# esp32-s2_ePaper_pcb_v1.net
KiCad netlist of a schematic drawn in EAGLE
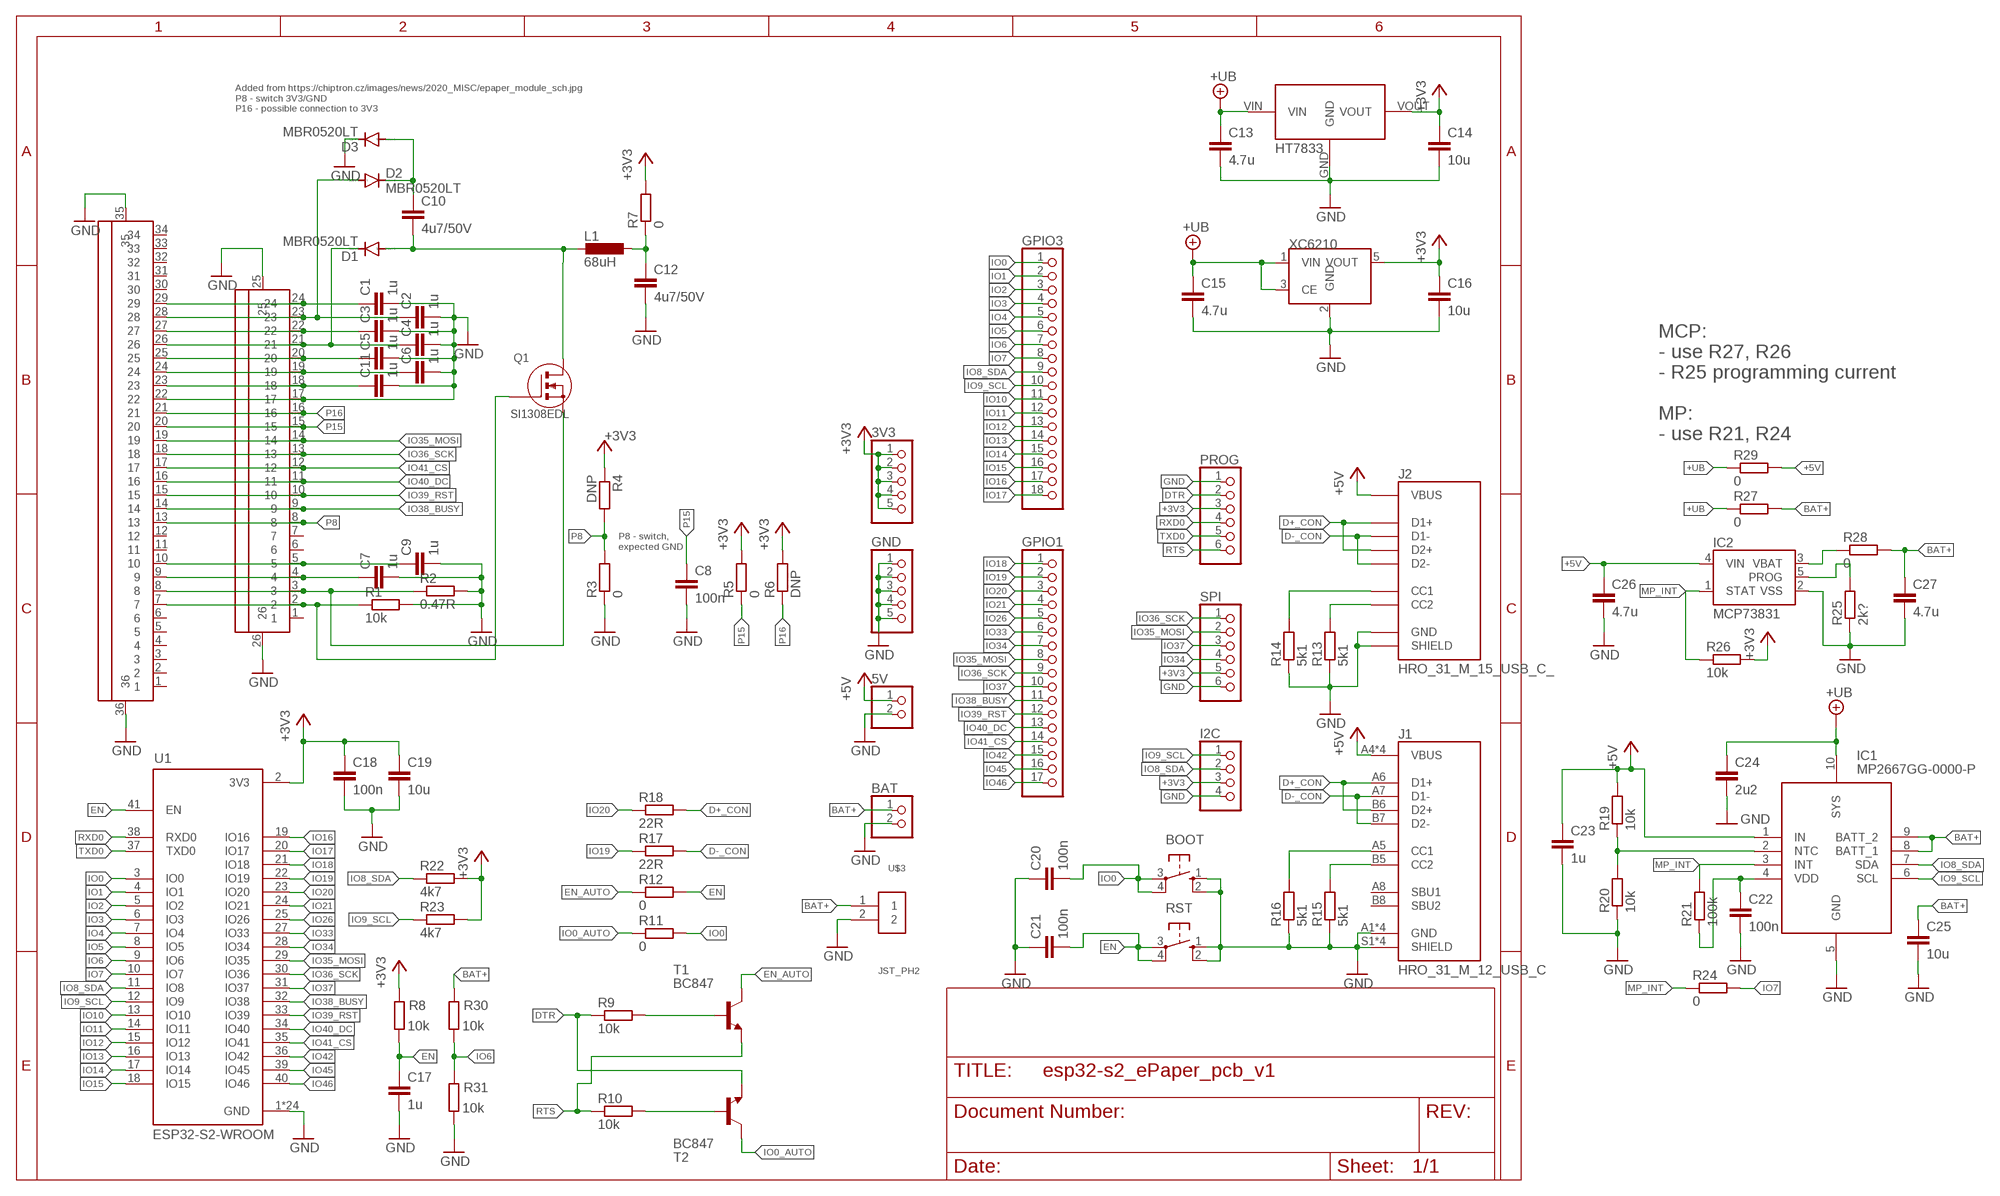
[diagram p0: schematic, sheet 1]

(export (version "E")
  (design (tool "Eeschema 10.0.6"))
  (components
    (comp (ref "3V3")
      (value "PINHD-1X5")
      (footprint "eagle-import:1X05")
      (libsource (lib "eagle-import") (part "PINHD-1X5"))
    )
    (comp (ref "5V")
      (value "PINHD-1X2")
      (footprint "eagle-import:1X02")
      (libsource (lib "eagle-import") (part "PINHD-1X2"))
    )
    (comp (ref "BAT")
      (value "PINHD-1X2")
      (footprint "eagle-import:1X02")
      (libsource (lib "eagle-import") (part "PINHD-1X2"))
    )
    (comp (ref "BOOT")
      (value "10-XX")
      (footprint "eagle-import:B3F-10XX")
      (fields (field (name "MPN") "B3F-1000"))
      (libsource (lib "eagle-import") (part "10-XX"))
    )
    (comp (ref "C1")
      (value "1u")
      (footprint "eagle-import:C0603K")
      (libsource (lib "eagle-import") (part "C-EUC0603K"))
    )
    (comp (ref "C2")
      (value "1u")
      (footprint "eagle-import:C0603K")
      (libsource (lib "eagle-import") (part "C-EUC0603K"))
    )
    (comp (ref "C3")
      (value "1u")
      (footprint "eagle-import:C0603K")
      (libsource (lib "eagle-import") (part "C-EUC0603K"))
    )
    (comp (ref "C4")
      (value "1u")
      (footprint "eagle-import:C0603K")
      (libsource (lib "eagle-import") (part "C-EUC0603K"))
    )
    (comp (ref "C5")
      (value "1u")
      (footprint "eagle-import:C0603K")
      (libsource (lib "eagle-import") (part "C-EUC0603K"))
    )
    (comp (ref "C6")
      (value "1u")
      (footprint "eagle-import:C0603K")
      (libsource (lib "eagle-import") (part "C-EUC0603K"))
    )
    (comp (ref "C7")
      (value "1u")
      (footprint "eagle-import:C0603K")
      (libsource (lib "eagle-import") (part "C-EUC0603K"))
    )
    (comp (ref "C8")
      (value "100n")
      (footprint "eagle-import:C0603K")
      (libsource (lib "eagle-import") (part "C-EUC0603K"))
    )
    (comp (ref "C9")
      (value "1u")
      (footprint "eagle-import:C0603K")
      (libsource (lib "eagle-import") (part "C-EUC0603K"))
    )
    (comp (ref "C10")
      (value "4u7/50V")
      (footprint "eagle-import:C1206")
      (libsource (lib "eagle-import") (part "C-EUC1206"))
    )
    (comp (ref "C11")
      (value "1u")
      (footprint "eagle-import:C0603K")
      (libsource (lib "eagle-import") (part "C-EUC0603K"))
    )
    (comp (ref "C12")
      (value "4u7/50V")
      (footprint "eagle-import:C1206")
      (libsource (lib "eagle-import") (part "C-EUC1206"))
    )
    (comp (ref "C13")
      (value "4.7u")
      (footprint "eagle-import:C1206")
      (libsource (lib "eagle-import") (part "C-EUC1206"))
    )
    (comp (ref "C14")
      (value "10u")
      (footprint "eagle-import:C1206")
      (libsource (lib "eagle-import") (part "C-EUC1206"))
    )
    (comp (ref "C15")
      (value "4.7u")
      (footprint "eagle-import:C1206")
      (libsource (lib "eagle-import") (part "C-EUC1206"))
    )
    (comp (ref "C16")
      (value "10u")
      (footprint "eagle-import:C1206")
      (libsource (lib "eagle-import") (part "C-EUC1206"))
    )
    (comp (ref "C17")
      (value "1u")
      (footprint "eagle-import:C0603K")
      (libsource (lib "eagle-import") (part "C-EUC0603K"))
    )
    (comp (ref "C18")
      (value "100n")
      (footprint "eagle-import:C0603K")
      (libsource (lib "eagle-import") (part "C-EUC0603K"))
    )
    (comp (ref "C19")
      (value "10u")
      (footprint "eagle-import:C1206")
      (libsource (lib "eagle-import") (part "C-EUC1206"))
    )
    (comp (ref "C20")
      (value "100n")
      (footprint "eagle-import:C0603K")
      (libsource (lib "eagle-import") (part "C-EUC0603K"))
    )
    (comp (ref "C21")
      (value "100n")
      (footprint "eagle-import:C0603K")
      (libsource (lib "eagle-import") (part "C-EUC0603K"))
    )
    (comp (ref "C22")
      (value "100n")
      (footprint "eagle-import:C0603K")
      (libsource (lib "eagle-import") (part "C-EUC0603K"))
    )
    (comp (ref "C23")
      (value "1u")
      (footprint "eagle-import:C0603K")
      (libsource (lib "eagle-import") (part "C-EUC0603K"))
    )
    (comp (ref "C24")
      (value "2u2")
      (footprint "eagle-import:C1206")
      (libsource (lib "eagle-import") (part "C-EUC1206"))
    )
    (comp (ref "C25")
      (value "10u")
      (footprint "eagle-import:C1206")
      (libsource (lib "eagle-import") (part "C-EUC1206"))
    )
    (comp (ref "C26")
      (value "4.7u")
      (footprint "eagle-import:C1206")
      (libsource (lib "eagle-import") (part "C-EUC1206"))
    )
    (comp (ref "C27")
      (value "4.7u")
      (footprint "eagle-import:C1206")
      (libsource (lib "eagle-import") (part "C-EUC1206"))
    )
    (comp (ref "D1")
      (value "MBR0520LT")
      (footprint "eagle-import:SOD123")
      (libsource (lib "eagle-import") (part "MBR0520LT"))
    )
    (comp (ref "D2")
      (value "MBR0520LT")
      (footprint "eagle-import:SOD123")
      (libsource (lib "eagle-import") (part "MBR0520LT"))
    )
    (comp (ref "D3")
      (value "MBR0520LT")
      (footprint "eagle-import:SOD123")
      (libsource (lib "eagle-import") (part "MBR0520LT"))
    )
    (comp (ref "GND")
      (value "PINHD-1X5")
      (footprint "eagle-import:1X05")
      (libsource (lib "eagle-import") (part "PINHD-1X5"))
    )
    (comp (ref "GPIO1")
      (value "PINHD-1X17")
      (footprint "eagle-import:1X17")
      (libsource (lib "eagle-import") (part "PINHD-1X17"))
    )
    (comp (ref "GPIO3")
      (value "PINHD-1X18")
      (footprint "eagle-import:1X18")
      (libsource (lib "eagle-import") (part "PINHD-1X18"))
    )
    (comp (ref "I2C")
      (value "PINHD-1X4")
      (footprint "eagle-import:1X04")
      (libsource (lib "eagle-import") (part "PINHD-1X4"))
    )
    (comp (ref "IC1")
      (value "MP2667GG-0000-P")
      (footprint "eagle-import:QFN50P200X200X105-10N")
      (fields (field (name "MOUSER_PART_NUMBER") "946-MP2667GG-0000-P"))
      (libsource (lib "eagle-import") (part "MP2667GG-0000-P"))
    )
    (comp (ref "IC2")
      (value "MCP73831")
      (footprint "eagle-import:SOT95P290X120-5")
      (libsource (lib "eagle-import") (part "MCP73831"))
    )
    (comp (ref "J1")
      (value "HRO_31_M_12_USB_C")
      (footprint "eagle-import:HRO_31_M_12_USB_C")
      (libsource (lib "eagle-import") (part "HRO_31_M_12_USB_C"))
    )
    (comp (ref "J2")
      (value "HRO_31_M_15_USB_C_")
      (footprint "eagle-import:HRO_31_M_15_USB_C")
      (libsource (lib "eagle-import") (part "HRO_31_M_15_USB_C_"))
    )
    (comp (ref "L1")
      (value "68uH")
      (footprint "eagle-import:L4532P")
      (libsource (lib "eagle-import") (part "L-EUL4532P"))
    )
    (comp (ref "PROG")
      (value "PINHD-1X6")
      (footprint "eagle-import:1X06")
      (libsource (lib "eagle-import") (part "PINHD-1X6"))
    )
    (comp (ref "Q1")
      (value "SI1308EDL")
      (footprint "eagle-import:SC-70")
      (libsource (lib "eagle-import") (part "SI1308EDL"))
    )
    (comp (ref "R1")
      (value "10k")
      (footprint "eagle-import:R0603")
      (libsource (lib "eagle-import") (part "R-EU_R0603"))
    )
    (comp (ref "R2")
      (value "0.47R")
      (footprint "eagle-import:R0603")
      (libsource (lib "eagle-import") (part "R-EU_R0603"))
    )
    (comp (ref "R3")
      (value "0")
      (footprint "eagle-import:R0603")
      (libsource (lib "eagle-import") (part "R-EU_R0603"))
    )
    (comp (ref "R4")
      (value "DNP")
      (footprint "eagle-import:R0603")
      (libsource (lib "eagle-import") (part "R-EU_R0603"))
    )
    (comp (ref "R5")
      (value "0")
      (footprint "eagle-import:R0603")
      (libsource (lib "eagle-import") (part "R-EU_R0603"))
    )
    (comp (ref "R6")
      (value "DNP")
      (footprint "eagle-import:R0603")
      (libsource (lib "eagle-import") (part "R-EU_R0603"))
    )
    (comp (ref "R7")
      (value "0")
      (footprint "eagle-import:R0603")
      (libsource (lib "eagle-import") (part "R-EU_R0603"))
    )
    (comp (ref "R8")
      (value "10k")
      (footprint "eagle-import:R0603")
      (libsource (lib "eagle-import") (part "R-EU_R0603"))
    )
    (comp (ref "R9")
      (value "10k")
      (footprint "eagle-import:R0603")
      (libsource (lib "eagle-import") (part "R-EU_R0603"))
    )
    (comp (ref "R10")
      (value "10k")
      (footprint "eagle-import:R0603")
      (libsource (lib "eagle-import") (part "R-EU_R0603"))
    )
    (comp (ref "R11")
      (value "0")
      (footprint "eagle-import:R0603")
      (libsource (lib "eagle-import") (part "R-EU_R0603"))
    )
    (comp (ref "R12")
      (value "0")
      (footprint "eagle-import:R0603")
      (libsource (lib "eagle-import") (part "R-EU_R0603"))
    )
    (comp (ref "R13")
      (value "5k1")
      (footprint "eagle-import:R0603")
      (libsource (lib "eagle-import") (part "R-EU_R0603"))
    )
    (comp (ref "R14")
      (value "5k1")
      (footprint "eagle-import:R0603")
      (libsource (lib "eagle-import") (part "R-EU_R0603"))
    )
    (comp (ref "R15")
      (value "5k1")
      (footprint "eagle-import:R0603")
      (libsource (lib "eagle-import") (part "R-EU_R0603"))
    )
    (comp (ref "R16")
      (value "5k1")
      (footprint "eagle-import:R0603")
      (libsource (lib "eagle-import") (part "R-EU_R0603"))
    )
    (comp (ref "R17")
      (value "22R")
      (footprint "eagle-import:R0603")
      (libsource (lib "eagle-import") (part "R-EU_R0603"))
    )
    (comp (ref "R18")
      (value "22R")
      (footprint "eagle-import:R0603")
      (libsource (lib "eagle-import") (part "R-EU_R0603"))
    )
    (comp (ref "R19")
      (value "10k")
      (footprint "eagle-import:R0603")
      (libsource (lib "eagle-import") (part "R-EU_R0603"))
    )
    (comp (ref "R20")
      (value "10k")
      (footprint "eagle-import:R0603")
      (libsource (lib "eagle-import") (part "R-EU_R0603"))
    )
    (comp (ref "R21")
      (value "100k")
      (footprint "eagle-import:R0603")
      (libsource (lib "eagle-import") (part "R-EU_R0603"))
    )
    (comp (ref "R22")
      (value "4k7")
      (footprint "eagle-import:R0603")
      (libsource (lib "eagle-import") (part "R-EU_R0603"))
    )
    (comp (ref "R23")
      (value "4k7")
      (footprint "eagle-import:R0603")
      (libsource (lib "eagle-import") (part "R-EU_R0603"))
    )
    (comp (ref "R24")
      (value "0")
      (footprint "eagle-import:R0603")
      (libsource (lib "eagle-import") (part "R-EU_R0603"))
    )
    (comp (ref "R25")
      (value "2k?")
      (footprint "eagle-import:R0603")
      (libsource (lib "eagle-import") (part "R-EU_R0603"))
    )
    (comp (ref "R26")
      (value "10k")
      (footprint "eagle-import:R0603")
      (libsource (lib "eagle-import") (part "R-EU_R0603"))
    )
    (comp (ref "R27")
      (value "0")
      (footprint "eagle-import:R0603")
      (libsource (lib "eagle-import") (part "R-EU_R0603"))
    )
    (comp (ref "R28")
      (value "0")
      (footprint "eagle-import:R0603")
      (libsource (lib "eagle-import") (part "R-EU_R0603"))
    )
    (comp (ref "R29")
      (value "0")
      (footprint "eagle-import:R0603")
      (libsource (lib "eagle-import") (part "R-EU_R0603"))
    )
    (comp (ref "R30")
      (value "10k")
      (footprint "eagle-import:R0603")
      (libsource (lib "eagle-import") (part "R-EU_R0603"))
    )
    (comp (ref "R31")
      (value "10k")
      (footprint "eagle-import:R0603")
      (libsource (lib "eagle-import") (part "R-EU_R0603"))
    )
    (comp (ref "RST")
      (value "10-XX")
      (footprint "eagle-import:B3F-10XX")
      (fields (field (name "MPN") "B3F-1000"))
      (libsource (lib "eagle-import") (part "10-XX"))
    )
    (comp (ref "SPI")
      (value "PINHD-1X6")
      (footprint "eagle-import:1X06")
      (libsource (lib "eagle-import") (part "PINHD-1X6"))
    )
    (comp (ref "T1")
      (value "BC847")
      (footprint "eagle-import:SOT23")
      (libsource (lib "eagle-import") (part "BC847"))
    )
    (comp (ref "T2")
      (value "BC847")
      (footprint "eagle-import:SOT23")
      (libsource (lib "eagle-import") (part "BC847"))
    )
    (comp (ref "U$1")
      (value "AYF532435_FPC_24PIN_0.5")
      (footprint "eagle-import:FPC_0.5_24PIN")
      (libsource (lib "eagle-import") (part "AYF532435_FPC_24PIN_0.5"))
    )
    (comp (ref "U$2")
      (value "AYF533435_FPC_34PIN_0.5")
      (footprint "eagle-import:FPC_0.5_34PIN")
      (libsource (lib "eagle-import") (part "AYF533435_FPC_34PIN_0.5"))
    )
    (comp (ref "U$3")
      (value "JST_PH2")
      (footprint "eagle-import:JSTPH2")
      (libsource (lib "eagle-import") (part "JST_PH2"))
    )
    (comp (ref "U1")
      (value "ESP32-S2-WROOM")
      (footprint "eagle-import:XCVR_ESP32-S2-WROOM")
      (fields (field (name "MF") "Espressif Systems"))
      (libsource (lib "eagle-import") (part "ESP32-S2-WROOM"))
    )
    (comp (ref "U2")
      (value "HT7833")
      (footprint "eagle-import:SOT89")
      (libsource (lib "eagle-import") (part "HT7833"))
    )
    (comp (ref "U3")
      (value "XC6210")
      (footprint "eagle-import:SOT-23-5")
      (libsource (lib "eagle-import") (part "XC6210"))
    )
  )
  (nets
    (net (code "1") (name "+3V3") (class "Default")
      (node (ref "3V3") (pin "1") (pinfunction "1_1") (pintype "passive"))
      (node (ref "3V3") (pin "2") (pinfunction "2_2") (pintype "passive"))
      (node (ref "3V3") (pin "3") (pinfunction "3_3") (pintype "passive"))
      (node (ref "3V3") (pin "4") (pinfunction "4_4") (pintype "passive"))
      (node (ref "3V3") (pin "5") (pinfunction "5_5") (pintype "passive"))
      (node (ref "C14") (pin "1") (pinfunction "1_1") (pintype "passive"))
      (node (ref "C16") (pin "1") (pinfunction "1_1") (pintype "passive"))
      (node (ref "C18") (pin "1") (pinfunction "1_1") (pintype "passive"))
      (node (ref "C19") (pin "1") (pinfunction "1_1") (pintype "passive"))
      (node (ref "I2C") (pin "3") (pinfunction "3_3") (pintype "passive"))
      (node (ref "PROG") (pin "3") (pinfunction "3_3") (pintype "passive"))
      (node (ref "R22") (pin "2") (pinfunction "2_2") (pintype "passive"))
      (node (ref "R23") (pin "2") (pinfunction "2_2") (pintype "passive"))
      (node (ref "R26") (pin "2") (pinfunction "2_2") (pintype "passive"))
      (node (ref "R4") (pin "1") (pinfunction "1_1") (pintype "passive"))
      (node (ref "R5") (pin "2") (pinfunction "2_2") (pintype "passive"))
      (node (ref "R6") (pin "2") (pinfunction "2_2") (pintype "passive"))
      (node (ref "R7") (pin "2") (pinfunction "2_2") (pintype "passive"))
      (node (ref "R8") (pin "2") (pinfunction "2_2") (pintype "passive"))
      (node (ref "SPI") (pin "5") (pinfunction "5_5") (pintype "passive"))
      (node (ref "U1") (pin "2") (pinfunction "3V3_2") (pintype "power_in"))
      (node (ref "U2") (pin "VOUT") (pinfunction "VOUT_VOUT") (pintype "bidirectional"))
      (node (ref "U3") (pin "5") (pinfunction "VOUT_5") (pintype "power_in"))
    )
    (net (code "2") (name "+5V") (class "Default")
      (node (ref "5V") (pin "1") (pinfunction "1_1") (pintype "passive"))
      (node (ref "C23") (pin "1") (pinfunction "1_1") (pintype "passive"))
      (node (ref "C26") (pin "1") (pinfunction "1_1") (pintype "passive"))
      (node (ref "IC1") (pin "1") (pinfunction "IN_1") (pintype "bidirectional"))
      (node (ref "IC2") (pin "4") (pinfunction "VIN_4") (pintype "power_in"))
      (node (ref "J1") (pin "A4") (pinfunction "VBUS_A4") (pintype "passive"))
      (node (ref "J1") (pin "A9") (pinfunction "VBUS_A9") (pintype "passive"))
      (node (ref "J1") (pin "B4") (pinfunction "VBUS_B4") (pintype "passive"))
      (node (ref "J1") (pin "B9") (pinfunction "VBUS_B9") (pintype "passive"))
      (node (ref "J2") (pin "P$13") (pinfunction "VBUS_P$13") (pintype "passive"))
      (node (ref "J2") (pin "P$2") (pinfunction "VBUS_P$2") (pintype "passive"))
      (node (ref "J2") (pin "P$6") (pinfunction "VBUS_P$6") (pintype "passive"))
      (node (ref "J2") (pin "P$9") (pinfunction "VBUS_P$9") (pintype "passive"))
      (node (ref "R19") (pin "2") (pinfunction "2_2") (pintype "passive"))
      (node (ref "R29") (pin "2") (pinfunction "2_2") (pintype "passive"))
    )
    (net (code "3") (name "+UB") (class "Default")
      (node (ref "C13") (pin "1") (pinfunction "1_1") (pintype "passive"))
      (node (ref "C15") (pin "1") (pinfunction "1_1") (pintype "passive"))
      (node (ref "C24") (pin "1") (pinfunction "1_1") (pintype "passive"))
      (node (ref "IC1") (pin "10") (pinfunction "SYS_10") (pintype "bidirectional"))
      (node (ref "R27") (pin "1") (pinfunction "1_1") (pintype "passive"))
      (node (ref "R29") (pin "1") (pinfunction "1_1") (pintype "passive"))
      (node (ref "U2") (pin "VIN") (pinfunction "VIN_VIN") (pintype "bidirectional"))
      (node (ref "U3") (pin "1") (pinfunction "VIN_1") (pintype "power_in"))
      (node (ref "U3") (pin "3") (pinfunction "CE_3") (pintype "power_in"))
    )
    (net (code "4") (name "BAT+") (class "Default")
      (node (ref "BAT") (pin "1") (pinfunction "1_1") (pintype "passive"))
      (node (ref "C25") (pin "1") (pinfunction "1_1") (pintype "passive"))
      (node (ref "C27") (pin "1") (pinfunction "1_1") (pintype "passive"))
      (node (ref "IC1") (pin "8") (pinfunction "BATT_1_8") (pintype "bidirectional"))
      (node (ref "IC1") (pin "9") (pinfunction "BATT_2_9") (pintype "bidirectional"))
      (node (ref "R27") (pin "2") (pinfunction "2_2") (pintype "passive"))
      (node (ref "R28") (pin "2") (pinfunction "2_2") (pintype "passive"))
      (node (ref "R30") (pin "2") (pinfunction "2_2") (pintype "passive"))
      (node (ref "U$3") (pin "1") (pinfunction "1_1") (pintype "bidirectional"))
    )
    (net (code "5") (name "D+_CON") (class "Default")
      (node (ref "J1") (pin "A6") (pinfunction "D1+_A6") (pintype "passive"))
      (node (ref "J1") (pin "B6") (pinfunction "D2+_B6") (pintype "passive"))
      (node (ref "J2") (pin "P$11") (pinfunction "D2+_P$11") (pintype "passive"))
      (node (ref "J2") (pin "P$4") (pinfunction "D1+_P$4") (pintype "passive"))
      (node (ref "R18") (pin "2") (pinfunction "2_2") (pintype "passive"))
    )
    (net (code "6") (name "D-_CON") (class "Default")
      (node (ref "J1") (pin "A7") (pinfunction "D1-_A7") (pintype "passive"))
      (node (ref "J1") (pin "B7") (pinfunction "D2-_B7") (pintype "passive"))
      (node (ref "J2") (pin "P$10") (pinfunction "D2-_P$10") (pintype "passive"))
      (node (ref "J2") (pin "P$3") (pinfunction "D1-_P$3") (pintype "passive"))
      (node (ref "R17") (pin "2") (pinfunction "2_2") (pintype "passive"))
    )
    (net (code "7") (name "DTR") (class "Default")
      (node (ref "PROG") (pin "2") (pinfunction "2_2") (pintype "passive"))
      (node (ref "R9") (pin "1") (pinfunction "1_1") (pintype "passive"))
      (node (ref "T2") (pin "2") (pinfunction "E_2") (pintype "passive"))
    )
    (net (code "8") (name "EN") (class "Default")
      (node (ref "C17") (pin "1") (pinfunction "1_1") (pintype "passive"))
      (node (ref "C21") (pin "2") (pinfunction "2_2") (pintype "passive"))
      (node (ref "R12") (pin "2") (pinfunction "2_2") (pintype "passive"))
      (node (ref "R8") (pin "1") (pinfunction "1_1") (pintype "passive"))
      (node (ref "RST") (pin "3") (pinfunction "P_3") (pintype "passive"))
      (node (ref "RST") (pin "4") (pinfunction "P1_4") (pintype "passive"))
      (node (ref "U1") (pin "41") (pinfunction "EN_41") (pintype "input"))
    )
    (net (code "9") (name "EN_AUTO") (class "Default")
      (node (ref "R12") (pin "1") (pinfunction "1_1") (pintype "passive"))
      (node (ref "T1") (pin "3") (pinfunction "C_3") (pintype "passive"))
    )
    (net (code "10") (name "GND") (class "Default")
      (node (ref "5V") (pin "2") (pinfunction "2_2") (pintype "passive"))
      (node (ref "BAT") (pin "2") (pinfunction "2_2") (pintype "passive"))
      (node (ref "BOOT") (pin "1") (pinfunction "S_1") (pintype "passive"))
      (node (ref "BOOT") (pin "2") (pinfunction "S1_2") (pintype "passive"))
      (node (ref "C1") (pin "2") (pinfunction "2_2") (pintype "passive"))
      (node (ref "C11") (pin "2") (pinfunction "2_2") (pintype "passive"))
      (node (ref "C12") (pin "2") (pinfunction "2_2") (pintype "passive"))
      (node (ref "C13") (pin "2") (pinfunction "2_2") (pintype "passive"))
      (node (ref "C14") (pin "2") (pinfunction "2_2") (pintype "passive"))
      (node (ref "C15") (pin "2") (pinfunction "2_2") (pintype "passive"))
      (node (ref "C16") (pin "2") (pinfunction "2_2") (pintype "passive"))
      (node (ref "C17") (pin "2") (pinfunction "2_2") (pintype "passive"))
      (node (ref "C18") (pin "2") (pinfunction "2_2") (pintype "passive"))
      (node (ref "C19") (pin "2") (pinfunction "2_2") (pintype "passive"))
      (node (ref "C2") (pin "2") (pinfunction "2_2") (pintype "passive"))
      (node (ref "C20") (pin "1") (pinfunction "1_1") (pintype "passive"))
      (node (ref "C21") (pin "1") (pinfunction "1_1") (pintype "passive"))
      (node (ref "C22") (pin "2") (pinfunction "2_2") (pintype "passive"))
      (node (ref "C23") (pin "2") (pinfunction "2_2") (pintype "passive"))
      (node (ref "C24") (pin "2") (pinfunction "2_2") (pintype "passive"))
      (node (ref "C25") (pin "2") (pinfunction "2_2") (pintype "passive"))
      (node (ref "C26") (pin "2") (pinfunction "2_2") (pintype "passive"))
      (node (ref "C27") (pin "2") (pinfunction "2_2") (pintype "passive"))
      (node (ref "C3") (pin "2") (pinfunction "2_2") (pintype "passive"))
      (node (ref "C4") (pin "2") (pinfunction "2_2") (pintype "passive"))
      (node (ref "C5") (pin "2") (pinfunction "2_2") (pintype "passive"))
      (node (ref "C6") (pin "2") (pinfunction "2_2") (pintype "passive"))
      (node (ref "C7") (pin "2") (pinfunction "2_2") (pintype "passive"))
      (node (ref "C8") (pin "2") (pinfunction "2_2") (pintype "passive"))
      (node (ref "C9") (pin "2") (pinfunction "2_2") (pintype "passive"))
      (node (ref "D3") (pin "C") (pinfunction "C_C") (pintype "passive"))
      (node (ref "GND") (pin "1") (pinfunction "1_1") (pintype "passive"))
      (node (ref "GND") (pin "2") (pinfunction "2_2") (pintype "passive"))
      (node (ref "GND") (pin "3") (pinfunction "3_3") (pintype "passive"))
      (node (ref "GND") (pin "4") (pinfunction "4_4") (pintype "passive"))
      (node (ref "GND") (pin "5") (pinfunction "5_5") (pintype "passive"))
      (node (ref "I2C") (pin "4") (pinfunction "4_4") (pintype "passive"))
      (node (ref "IC1") (pin "5") (pinfunction "GND_5") (pintype "bidirectional"))
      (node (ref "IC2") (pin "2") (pinfunction "VSS_2") (pintype "power_in"))
      (node (ref "J1") (pin "A1") (pinfunction "GND_A1") (pintype "passive"))
      (node (ref "J1") (pin "A12") (pinfunction "GND_A12") (pintype "passive"))
      (node (ref "J1") (pin "B1") (pinfunction "GND_B1") (pintype "passive"))
      (node (ref "J1") (pin "B12") (pinfunction "GND_B12") (pintype "passive"))
      (node (ref "J1") (pin "S1") (pinfunction "SHIELD_S1") (pintype "passive"))
      (node (ref "J1") (pin "S2") (pinfunction "SHIELD_S2") (pintype "passive"))
      (node (ref "J1") (pin "S3") (pinfunction "SHIELD_S3") (pintype "passive"))
      (node (ref "J1") (pin "S4") (pinfunction "SHIELD_S4") (pintype "passive"))
      (node (ref "J2") (pin "P$1") (pinfunction "GND_P$1") (pintype "passive"))
      (node (ref "J2") (pin "P$14") (pinfunction "GND_P$14") (pintype "passive"))
      (node (ref "J2") (pin "P$15") (pinfunction "SHIELD_P$15") (pintype "passive"))
      (node (ref "J2") (pin "P$16") (pinfunction "SHIELD_P$16") (pintype "passive"))
      (node (ref "J2") (pin "P$17") (pinfunction "SHIELD_P$17") (pintype "passive"))
      (node (ref "J2") (pin "P$18") (pinfunction "SHIELD_P$18") (pintype "passive"))
      (node (ref "J2") (pin "P$7") (pinfunction "GND_P$7") (pintype "passive"))
      (node (ref "J2") (pin "P$8") (pinfunction "GND_P$8") (pintype "passive"))
      (node (ref "PROG") (pin "1") (pinfunction "1_1") (pintype "passive"))
      (node (ref "R1") (pin "2") (pinfunction "2_2") (pintype "passive"))
      (node (ref "R13") (pin "1") (pinfunction "1_1") (pintype "passive"))
      (node (ref "R14") (pin "1") (pinfunction "1_1") (pintype "passive"))
      (node (ref "R15") (pin "1") (pinfunction "1_1") (pintype "passive"))
      (node (ref "R16") (pin "1") (pinfunction "1_1") (pintype "passive"))
      (node (ref "R2") (pin "2") (pinfunction "2_2") (pintype "passive"))
      (node (ref "R20") (pin "1") (pinfunction "1_1") (pintype "passive"))
      (node (ref "R25") (pin "1") (pinfunction "1_1") (pintype "passive"))
      (node (ref "R3") (pin "1") (pinfunction "1_1") (pintype "passive"))
      (node (ref "R31") (pin "1") (pinfunction "1_1") (pintype "passive"))
      (node (ref "RST") (pin "1") (pinfunction "S_1") (pintype "passive"))
      (node (ref "RST") (pin "2") (pinfunction "S1_2") (pintype "passive"))
      (node (ref "SPI") (pin "6") (pinfunction "6_6") (pintype "passive"))
      (node (ref "U$1") (pin "17") (pinfunction "17_17") (pintype "bidirectional"))
      (node (ref "U$1") (pin "25") (pinfunction "25_25") (pintype "power_in"))
      (node (ref "U$1") (pin "26") (pinfunction "26_26") (pintype "power_in"))
      (node (ref "U$2") (pin "22") (pinfunction "22_22") (pintype "bidirectional"))
      (node (ref "U$2") (pin "35") (pinfunction "35_35") (pintype "power_in"))
      (node (ref "U$2") (pin "36") (pinfunction "36_36") (pintype "power_in"))
      (node (ref "U$3") (pin "2") (pinfunction "2_2") (pintype "bidirectional"))
      (node (ref "U1") (pin "1") (pinfunction "GND_1") (pintype "power_in"))
      (node (ref "U1") (pin "26") (pinfunction "GND_26") (pintype "power_in"))
      (node (ref "U1") (pin "42") (pinfunction "GND_42") (pintype "power_in"))
      (node (ref "U1") (pin "43.1") (pinfunction "GND_43.1") (pintype "power_in"))
      (node (ref "U1") (pin "43.10") (pinfunction "GND_43.10") (pintype "power_in"))
      (node (ref "U1") (pin "43.11") (pinfunction "GND_43.11") (pintype "power_in"))
      (node (ref "U1") (pin "43.12") (pinfunction "GND_43.12") (pintype "power_in"))
      (node (ref "U1") (pin "43.13") (pinfunction "GND_43.13") (pintype "power_in"))
      (node (ref "U1") (pin "43.14") (pinfunction "GND_43.14") (pintype "power_in"))
      (node (ref "U1") (pin "43.15") (pinfunction "GND_43.15") (pintype "power_in"))
      (node (ref "U1") (pin "43.16") (pinfunction "GND_43.16") (pintype "power_in"))
      (node (ref "U1") (pin "43.17") (pinfunction "GND_43.17") (pintype "power_in"))
      (node (ref "U1") (pin "43.18") (pinfunction "GND_43.18") (pintype "power_in"))
      (node (ref "U1") (pin "43.19") (pinfunction "GND_43.19") (pintype "power_in"))
      (node (ref "U1") (pin "43.2") (pinfunction "GND_43.2") (pintype "power_in"))
      (node (ref "U1") (pin "43.20") (pinfunction "GND_43.20") (pintype "power_in"))
      (node (ref "U1") (pin "43.21") (pinfunction "GND_43.21") (pintype "power_in"))
      (node (ref "U1") (pin "43.3") (pinfunction "GND_43.3") (pintype "power_in"))
      (node (ref "U1") (pin "43.4") (pinfunction "GND_43.4") (pintype "power_in"))
      (node (ref "U1") (pin "43.5") (pinfunction "GND_43.5") (pintype "power_in"))
      (node (ref "U1") (pin "43.6") (pinfunction "GND_43.6") (pintype "power_in"))
      (node (ref "U1") (pin "43.7") (pinfunction "GND_43.7") (pintype "power_in"))
      (node (ref "U1") (pin "43.8") (pinfunction "GND_43.8") (pintype "power_in"))
      (node (ref "U1") (pin "43.9") (pinfunction "GND_43.9") (pintype "power_in"))
      (node (ref "U2") (pin "GND") (pinfunction "GND_GND") (pintype "bidirectional"))
      (node (ref "U3") (pin "2") (pinfunction "GND_2") (pintype "power_in"))
    )
    (net (code "11") (name "IO0") (class "Default")
      (node (ref "BOOT") (pin "3") (pinfunction "P_3") (pintype "passive"))
      (node (ref "BOOT") (pin "4") (pinfunction "P1_4") (pintype "passive"))
      (node (ref "C20") (pin "2") (pinfunction "2_2") (pintype "passive"))
      (node (ref "GPIO3") (pin "1") (pinfunction "1_1") (pintype "passive"))
      (node (ref "R11") (pin "2") (pinfunction "2_2") (pintype "passive"))
      (node (ref "U1") (pin "3") (pinfunction "IO0_3") (pintype "bidirectional"))
    )
    (net (code "12") (name "IO0_AUTO") (class "Default")
      (node (ref "R11") (pin "1") (pinfunction "1_1") (pintype "passive"))
      (node (ref "T2") (pin "3") (pinfunction "C_3") (pintype "passive"))
    )
    (net (code "13") (name "IO1") (class "Default")
      (node (ref "GPIO3") (pin "2") (pinfunction "2_2") (pintype "passive"))
      (node (ref "U1") (pin "4") (pinfunction "IO1_4") (pintype "bidirectional"))
    )
    (net (code "14") (name "IO2") (class "Default")
      (node (ref "GPIO3") (pin "3") (pinfunction "3_3") (pintype "passive"))
      (node (ref "U1") (pin "5") (pinfunction "IO2_5") (pintype "bidirectional"))
    )
    (net (code "15") (name "IO3") (class "Default")
      (node (ref "GPIO3") (pin "4") (pinfunction "4_4") (pintype "passive"))
      (node (ref "U1") (pin "6") (pinfunction "IO3_6") (pintype "bidirectional"))
    )
    (net (code "16") (name "IO4") (class "Default")
      (node (ref "GPIO3") (pin "5") (pinfunction "5_5") (pintype "passive"))
      (node (ref "U1") (pin "7") (pinfunction "IO4_7") (pintype "bidirectional"))
    )
    (net (code "17") (name "IO5") (class "Default")
      (node (ref "GPIO3") (pin "6") (pinfunction "6_6") (pintype "passive"))
      (node (ref "U1") (pin "8") (pinfunction "IO5_8") (pintype "bidirectional"))
    )
    (net (code "18") (name "IO6") (class "Default")
      (node (ref "GPIO3") (pin "7") (pinfunction "7_7") (pintype "passive"))
      (node (ref "R30") (pin "1") (pinfunction "1_1") (pintype "passive"))
      (node (ref "R31") (pin "2") (pinfunction "2_2") (pintype "passive"))
      (node (ref "U1") (pin "9") (pinfunction "IO6_9") (pintype "bidirectional"))
    )
    (net (code "19") (name "IO7") (class "Default")
      (node (ref "GPIO3") (pin "8") (pinfunction "8_8") (pintype "passive"))
      (node (ref "R24") (pin "2") (pinfunction "2_2") (pintype "passive"))
      (node (ref "U1") (pin "10") (pinfunction "IO7_10") (pintype "bidirectional"))
    )
    (net (code "20") (name "IO8_SDA") (class "Default")
      (node (ref "GPIO3") (pin "9") (pinfunction "9_9") (pintype "passive"))
      (node (ref "I2C") (pin "2") (pinfunction "2_2") (pintype "passive"))
      (node (ref "IC1") (pin "7") (pinfunction "SDA_7") (pintype "bidirectional"))
      (node (ref "R22") (pin "1") (pinfunction "1_1") (pintype "passive"))
      (node (ref "U1") (pin "11") (pinfunction "IO8_11") (pintype "bidirectional"))
    )
    (net (code "21") (name "IO9_SCL") (class "Default")
      (node (ref "GPIO3") (pin "10") (pinfunction "10_10") (pintype "passive"))
      (node (ref "I2C") (pin "1") (pinfunction "1_1") (pintype "passive"))
      (node (ref "IC1") (pin "6") (pinfunction "SCL_6") (pintype "bidirectional"))
      (node (ref "R23") (pin "1") (pinfunction "1_1") (pintype "passive"))
      (node (ref "U1") (pin "12") (pinfunction "IO9_12") (pintype "bidirectional"))
    )
    (net (code "22") (name "IO10") (class "Default")
      (node (ref "GPIO3") (pin "11") (pinfunction "11_11") (pintype "passive"))
      (node (ref "U1") (pin "13") (pinfunction "IO10_13") (pintype "bidirectional"))
    )
    (net (code "23") (name "IO11") (class "Default")
      (node (ref "GPIO3") (pin "12") (pinfunction "12_12") (pintype "passive"))
      (node (ref "U1") (pin "14") (pinfunction "IO11_14") (pintype "bidirectional"))
    )
    (net (code "24") (name "IO12") (class "Default")
      (node (ref "GPIO3") (pin "13") (pinfunction "13_13") (pintype "passive"))
      (node (ref "U1") (pin "15") (pinfunction "IO12_15") (pintype "bidirectional"))
    )
    (net (code "25") (name "IO13") (class "Default")
      (node (ref "GPIO3") (pin "14") (pinfunction "14_14") (pintype "passive"))
      (node (ref "U1") (pin "16") (pinfunction "IO13_16") (pintype "bidirectional"))
    )
    (net (code "26") (name "IO14") (class "Default")
      (node (ref "GPIO3") (pin "15") (pinfunction "15_15") (pintype "passive"))
      (node (ref "U1") (pin "17") (pinfunction "IO14_17") (pintype "bidirectional"))
    )
    (net (code "27") (name "IO15") (class "Default")
      (node (ref "GPIO3") (pin "16") (pinfunction "16_16") (pintype "passive"))
      (node (ref "U1") (pin "18") (pinfunction "IO15_18") (pintype "bidirectional"))
    )
    (net (code "28") (name "IO16") (class "Default")
      (node (ref "GPIO3") (pin "17") (pinfunction "17_17") (pintype "passive"))
      (node (ref "U1") (pin "19") (pinfunction "IO16_19") (pintype "bidirectional"))
    )
    (net (code "29") (name "IO17") (class "Default")
      (node (ref "GPIO3") (pin "18") (pinfunction "18_18") (pintype "passive"))
      (node (ref "U1") (pin "20") (pinfunction "IO17_20") (pintype "bidirectional"))
    )
    (net (code "30") (name "IO18") (class "Default")
      (node (ref "GPIO1") (pin "1") (pinfunction "1_1") (pintype "passive"))
      (node (ref "U1") (pin "21") (pinfunction "IO18_21") (pintype "bidirectional"))
    )
    (net (code "31") (name "IO19") (class "Default")
      (node (ref "GPIO1") (pin "2") (pinfunction "2_2") (pintype "passive"))
      (node (ref "R17") (pin "1") (pinfunction "1_1") (pintype "passive"))
      (node (ref "U1") (pin "22") (pinfunction "IO19_22") (pintype "bidirectional"))
    )
    (net (code "32") (name "IO20") (class "Default")
      (node (ref "GPIO1") (pin "3") (pinfunction "3_3") (pintype "passive"))
      (node (ref "R18") (pin "1") (pinfunction "1_1") (pintype "passive"))
      (node (ref "U1") (pin "23") (pinfunction "IO20_23") (pintype "bidirectional"))
    )
    (net (code "33") (name "IO21") (class "Default")
      (node (ref "GPIO1") (pin "4") (pinfunction "4_4") (pintype "passive"))
      (node (ref "U1") (pin "24") (pinfunction "IO21_24") (pintype "bidirectional"))
    )
    (net (code "34") (name "IO26") (class "Default")
      (node (ref "GPIO1") (pin "5") (pinfunction "5_5") (pintype "passive"))
      (node (ref "U1") (pin "25") (pinfunction "IO26_25") (pintype "bidirectional"))
    )
    (net (code "35") (name "IO33") (class "Default")
      (node (ref "GPIO1") (pin "6") (pinfunction "6_6") (pintype "passive"))
      (node (ref "U1") (pin "27") (pinfunction "IO33_27") (pintype "bidirectional"))
    )
    (net (code "36") (name "IO34") (class "Default")
      (node (ref "GPIO1") (pin "7") (pinfunction "7_7") (pintype "passive"))
      (node (ref "SPI") (pin "4") (pinfunction "4_4") (pintype "passive"))
      (node (ref "U1") (pin "28") (pinfunction "IO34_28") (pintype "bidirectional"))
    )
    (net (code "37") (name "IO35_MOSI") (class "Default")
      (node (ref "GPIO1") (pin "8") (pinfunction "8_8") (pintype "passive"))
      (node (ref "SPI") (pin "2") (pinfunction "2_2") (pintype "passive"))
      (node (ref "U$1") (pin "14") (pinfunction "14_14") (pintype "bidirectional"))
      (node (ref "U$2") (pin "19") (pinfunction "19_19") (pintype "bidirectional"))
      (node (ref "U1") (pin "29") (pinfunction "IO35_29") (pintype "bidirectional"))
    )
    (net (code "38") (name "IO36_SCK") (class "Default")
      (node (ref "GPIO1") (pin "9") (pinfunction "9_9") (pintype "passive"))
      (node (ref "SPI") (pin "1") (pinfunction "1_1") (pintype "passive"))
      (node (ref "U$1") (pin "13") (pinfunction "13_13") (pintype "bidirectional"))
      (node (ref "U$2") (pin "18") (pinfunction "18_18") (pintype "bidirectional"))
      (node (ref "U1") (pin "30") (pinfunction "IO36_30") (pintype "bidirectional"))
    )
    (net (code "39") (name "IO37") (class "Default")
      (node (ref "GPIO1") (pin "10") (pinfunction "10_10") (pintype "passive"))
      (node (ref "SPI") (pin "3") (pinfunction "3_3") (pintype "passive"))
      (node (ref "U1") (pin "31") (pinfunction "IO37_31") (pintype "bidirectional"))
    )
    (net (code "40") (name "IO38_BUSY") (class "Default")
      (node (ref "GPIO1") (pin "11") (pinfunction "11_11") (pintype "passive"))
      (node (ref "U$1") (pin "9") (pinfunction "9_9") (pintype "bidirectional"))
      (node (ref "U$2") (pin "14") (pinfunction "14_14") (pintype "bidirectional"))
      (node (ref "U1") (pin "32") (pinfunction "IO38_32") (pintype "bidirectional"))
    )
    (net (code "41") (name "IO39_RST") (class "Default")
      (node (ref "GPIO1") (pin "12") (pinfunction "12_12") (pintype "passive"))
      (node (ref "U$1") (pin "10") (pinfunction "10_10") (pintype "bidirectional"))
      (node (ref "U$2") (pin "15") (pinfunction "15_15") (pintype "bidirectional"))
      (node (ref "U1") (pin "33") (pinfunction "IO39_33") (pintype "bidirectional"))
    )
    (net (code "42") (name "IO40_DC") (class "Default")
      (node (ref "GPIO1") (pin "13") (pinfunction "13_13") (pintype "passive"))
      (node (ref "U$1") (pin "11") (pinfunction "11_11") (pintype "bidirectional"))
      (node (ref "U$2") (pin "16") (pinfunction "16_16") (pintype "bidirectional"))
      (node (ref "U1") (pin "34") (pinfunction "IO40_34") (pintype "bidirectional"))
    )
    (net (code "43") (name "IO41_CS") (class "Default")
      (node (ref "GPIO1") (pin "14") (pinfunction "14_14") (pintype "passive"))
      (node (ref "U$1") (pin "12") (pinfunction "12_12") (pintype "bidirectional"))
      (node (ref "U$2") (pin "17") (pinfunction "17_17") (pintype "bidirectional"))
      (node (ref "U1") (pin "35") (pinfunction "IO41_35") (pintype "bidirectional"))
    )
    (net (code "44") (name "IO42") (class "Default")
      (node (ref "GPIO1") (pin "15") (pinfunction "15_15") (pintype "passive"))
      (node (ref "U1") (pin "36") (pinfunction "IO42_36") (pintype "bidirectional"))
    )
    (net (code "45") (name "IO45") (class "Default")
      (node (ref "GPIO1") (pin "16") (pinfunction "16_16") (pintype "passive"))
      (node (ref "U1") (pin "39") (pinfunction "IO45_39") (pintype "bidirectional"))
    )
    (net (code "46") (name "IO46") (class "Default")
      (node (ref "GPIO1") (pin "17") (pinfunction "17_17") (pintype "passive"))
      (node (ref "U1") (pin "40") (pinfunction "IO46_40") (pintype "bidirectional"))
    )
    (net (code "47") (name "MP_INT") (class "Default")
      (node (ref "IC1") (pin "3") (pinfunction "INT_3") (pintype "bidirectional"))
      (node (ref "IC2") (pin "1") (pinfunction "STAT_1") (pintype "output"))
      (node (ref "R21") (pin "2") (pinfunction "2_2") (pintype "passive"))
      (node (ref "R24") (pin "1") (pinfunction "1_1") (pintype "passive"))
      (node (ref "R26") (pin "1") (pinfunction "1_1") (pintype "passive"))
    )
    (net (code "48") (name "Net-(C1-Pad1)") (class "Default")
      (node (ref "C1") (pin "1") (pinfunction "1_1") (pintype "passive"))
      (node (ref "U$1") (pin "24") (pinfunction "24_24") (pintype "bidirectional"))
      (node (ref "U$2") (pin "29") (pinfunction "29_29") (pintype "bidirectional"))
    )
    (net (code "49") (name "Net-(C2-Pad1)") (class "Default")
      (node (ref "C2") (pin "1") (pinfunction "1_1") (pintype "passive"))
      (node (ref "D2") (pin "A") (pinfunction "A_A") (pintype "passive"))
      (node (ref "U$1") (pin "23") (pinfunction "23_23") (pintype "bidirectional"))
      (node (ref "U$2") (pin "28") (pinfunction "28_28") (pintype "bidirectional"))
    )
    (net (code "50") (name "Net-(C3-Pad1)") (class "Default")
      (node (ref "C3") (pin "1") (pinfunction "1_1") (pintype "passive"))
      (node (ref "U$1") (pin "22") (pinfunction "22_22") (pintype "bidirectional"))
      (node (ref "U$2") (pin "27") (pinfunction "27_27") (pintype "bidirectional"))
    )
    (net (code "51") (name "Net-(C4-Pad1)") (class "Default")
      (node (ref "C4") (pin "1") (pinfunction "1_1") (pintype "passive"))
      (node (ref "D1") (pin "C") (pinfunction "C_C") (pintype "passive"))
      (node (ref "U$1") (pin "21") (pinfunction "21_21") (pintype "bidirectional"))
      (node (ref "U$2") (pin "26") (pinfunction "26_26") (pintype "bidirectional"))
    )
    (net (code "52") (name "Net-(C5-Pad1)") (class "Default")
      (node (ref "C5") (pin "1") (pinfunction "1_1") (pintype "passive"))
      (node (ref "U$1") (pin "20") (pinfunction "20_20") (pintype "bidirectional"))
      (node (ref "U$2") (pin "25") (pinfunction "25_25") (pintype "bidirectional"))
    )
    (net (code "53") (name "Net-(C6-Pad1)") (class "Default")
      (node (ref "C6") (pin "1") (pinfunction "1_1") (pintype "passive"))
      (node (ref "U$1") (pin "19") (pinfunction "19_19") (pintype "bidirectional"))
      (node (ref "U$2") (pin "24") (pinfunction "24_24") (pintype "bidirectional"))
    )
    (net (code "54") (name "Net-(C7-Pad1)") (class "Default")
      (node (ref "C7") (pin "1") (pinfunction "1_1") (pintype "passive"))
      (node (ref "U$1") (pin "4") (pinfunction "4_4") (pintype "bidirectional"))
      (node (ref "U$2") (pin "9") (pinfunction "9_9") (pintype "bidirectional"))
    )
    (net (code "55") (name "Net-(C9-Pad1)") (class "Default")
      (node (ref "C9") (pin "1") (pinfunction "1_1") (pintype "passive"))
      (node (ref "U$1") (pin "5") (pinfunction "5_5") (pintype "bidirectional"))
      (node (ref "U$2") (pin "10") (pinfunction "10_10") (pintype "bidirectional"))
    )
    (net (code "56") (name "Net-(C10-Pad1)") (class "Default")
      (node (ref "C10") (pin "1") (pinfunction "1_1") (pintype "passive"))
      (node (ref "D2") (pin "C") (pinfunction "C_C") (pintype "passive"))
      (node (ref "D3") (pin "A") (pinfunction "A_A") (pintype "passive"))
    )
    (net (code "57") (name "Net-(C11-Pad1)") (class "Default")
      (node (ref "C11") (pin "1") (pinfunction "1_1") (pintype "passive"))
      (node (ref "U$1") (pin "18") (pinfunction "18_18") (pintype "bidirectional"))
      (node (ref "U$2") (pin "23") (pinfunction "23_23") (pintype "bidirectional"))
    )
    (net (code "58") (name "Net-(C12-Pad1)") (class "Default")
      (node (ref "C12") (pin "1") (pinfunction "1_1") (pintype "passive"))
      (node (ref "L1") (pin "1") (pinfunction "1_1") (pintype "passive"))
      (node (ref "R7") (pin "1") (pinfunction "1_1") (pintype "passive"))
    )
    (net (code "59") (name "Net-(IC1-NTC)") (class "Default")
      (node (ref "IC1") (pin "2") (pinfunction "NTC_2") (pintype "bidirectional"))
      (node (ref "R19") (pin "1") (pinfunction "1_1") (pintype "passive"))
      (node (ref "R20") (pin "2") (pinfunction "2_2") (pintype "passive"))
    )
    (net (code "60") (name "Net-(IC1-VDD)") (class "Default")
      (node (ref "C22") (pin "1") (pinfunction "1_1") (pintype "passive"))
      (node (ref "IC1") (pin "4") (pinfunction "VDD_4") (pintype "bidirectional"))
      (node (ref "R21") (pin "1") (pinfunction "1_1") (pintype "passive"))
    )
    (net (code "61") (name "Net-(IC2-PROG)") (class "Default")
      (node (ref "IC2") (pin "5") (pinfunction "PROG_5") (pintype "input"))
      (node (ref "R25") (pin "2") (pinfunction "2_2") (pintype "passive"))
    )
    (net (code "62") (name "Net-(IC2-VBAT)") (class "Default")
      (node (ref "IC2") (pin "3") (pinfunction "VBAT_3") (pintype "power_in"))
      (node (ref "R28") (pin "1") (pinfunction "1_1") (pintype "passive"))
    )
    (net (code "63") (name "Net-(J1-CC1)") (class "Default")
      (node (ref "J1") (pin "A5") (pinfunction "CC1_A5") (pintype "passive"))
      (node (ref "R16") (pin "2") (pinfunction "2_2") (pintype "passive"))
    )
    (net (code "64") (name "Net-(J1-CC2)") (class "Default")
      (node (ref "J1") (pin "B5") (pinfunction "CC2_B5") (pintype "passive"))
      (node (ref "R15") (pin "2") (pinfunction "2_2") (pintype "passive"))
    )
    (net (code "65") (name "Net-(J2-CC1)") (class "Default")
      (node (ref "J2") (pin "P$5") (pinfunction "CC1_P$5") (pintype "passive"))
      (node (ref "R14") (pin "2") (pinfunction "2_2") (pintype "passive"))
    )
    (net (code "66") (name "Net-(J2-CC2)") (class "Default")
      (node (ref "J2") (pin "P$12") (pinfunction "CC2_P$12") (pintype "passive"))
      (node (ref "R13") (pin "2") (pinfunction "2_2") (pintype "passive"))
    )
    (net (code "67") (name "Net-(Q1-D)") (class "Default")
      (node (ref "C10") (pin "2") (pinfunction "2_2") (pintype "passive"))
      (node (ref "D1") (pin "A") (pinfunction "A_A") (pintype "passive"))
      (node (ref "L1") (pin "2") (pinfunction "2_2") (pintype "passive"))
      (node (ref "Q1") (pin "3") (pinfunction "D_3") (pintype "passive"))
    )
    (net (code "68") (name "Net-(Q1-G)") (class "Default")
      (node (ref "Q1") (pin "1") (pinfunction "G_1") (pintype "passive"))
      (node (ref "R1") (pin "1") (pinfunction "1_1") (pintype "passive"))
      (node (ref "U$1") (pin "2") (pinfunction "2_2") (pintype "bidirectional"))
      (node (ref "U$2") (pin "7") (pinfunction "7_7") (pintype "bidirectional"))
    )
    (net (code "69") (name "Net-(Q1-S)") (class "Default")
      (node (ref "Q1") (pin "2") (pinfunction "S_2") (pintype "passive"))
      (node (ref "R2") (pin "1") (pinfunction "1_1") (pintype "passive"))
      (node (ref "U$1") (pin "3") (pinfunction "3_3") (pintype "bidirectional"))
      (node (ref "U$2") (pin "8") (pinfunction "8_8") (pintype "bidirectional"))
    )
    (net (code "70") (name "Net-(T1-B)") (class "Default")
      (node (ref "R9") (pin "2") (pinfunction "2_2") (pintype "passive"))
      (node (ref "T1") (pin "1") (pinfunction "B_1") (pintype "passive"))
    )
    (net (code "71") (name "Net-(T2-B)") (class "Default")
      (node (ref "R10") (pin "2") (pinfunction "2_2") (pintype "passive"))
      (node (ref "T2") (pin "1") (pinfunction "B_1") (pintype "passive"))
    )
    (net (code "72") (name "P8") (class "Default")
      (node (ref "R3") (pin "2") (pinfunction "2_2") (pintype "passive"))
      (node (ref "R4") (pin "2") (pinfunction "2_2") (pintype "passive"))
      (node (ref "U$1") (pin "8") (pinfunction "8_8") (pintype "bidirectional"))
      (node (ref "U$2") (pin "13") (pinfunction "13_13") (pintype "bidirectional"))
    )
    (net (code "73") (name "P15") (class "Default")
      (node (ref "C8") (pin "1") (pinfunction "1_1") (pintype "passive"))
      (node (ref "R5") (pin "1") (pinfunction "1_1") (pintype "passive"))
      (node (ref "U$1") (pin "15") (pinfunction "15_15") (pintype "bidirectional"))
      (node (ref "U$2") (pin "20") (pinfunction "20_20") (pintype "bidirectional"))
    )
    (net (code "74") (name "P16") (class "Default")
      (node (ref "R6") (pin "1") (pinfunction "1_1") (pintype "passive"))
      (node (ref "U$1") (pin "16") (pinfunction "16_16") (pintype "bidirectional"))
      (node (ref "U$2") (pin "21") (pinfunction "21_21") (pintype "bidirectional"))
    )
    (net (code "75") (name "RTS") (class "Default")
      (node (ref "PROG") (pin "6") (pinfunction "6_6") (pintype "passive"))
      (node (ref "R10") (pin "1") (pinfunction "1_1") (pintype "passive"))
      (node (ref "T1") (pin "2") (pinfunction "E_2") (pintype "passive"))
    )
    (net (code "76") (name "RXD0") (class "Default")
      (node (ref "PROG") (pin "4") (pinfunction "4_4") (pintype "passive"))
      (node (ref "U1") (pin "38") (pinfunction "RXD0_38") (pintype "bidirectional"))
    )
    (net (code "77") (name "TXD0") (class "Default")
      (node (ref "PROG") (pin "5") (pinfunction "5_5") (pintype "passive"))
      (node (ref "U1") (pin "37") (pinfunction "TXD0_37") (pintype "bidirectional"))
    )
    (net (code "78") (name "unconnected-(J1-SBU1-PadA8)") (class "Default")
      (node (ref "J1") (pin "A8") (pinfunction "SBU1_A8") (pintype "passive"))
    )
    (net (code "79") (name "unconnected-(J1-SBU2-PadB8)") (class "Default")
      (node (ref "J1") (pin "B8") (pinfunction "SBU2_B8") (pintype "passive"))
    )
    (net (code "80") (name "unconnected-(U$1-Pad1)") (class "Default")
      (node (ref "U$1") (pin "1") (pinfunction "1_1") (pintype "bidirectional"))
    )
    (net (code "81") (name "unconnected-(U$1-Pad6)") (class "Default")
      (node (ref "U$1") (pin "6") (pinfunction "6_6") (pintype "bidirectional"))
    )
    (net (code "82") (name "unconnected-(U$1-Pad7)") (class "Default")
      (node (ref "U$1") (pin "7") (pinfunction "7_7") (pintype "bidirectional"))
    )
    (net (code "83") (name "unconnected-(U$2-Pad1)") (class "Default")
      (node (ref "U$2") (pin "1") (pinfunction "1_1") (pintype "bidirectional"))
    )
    (net (code "84") (name "unconnected-(U$2-Pad2)") (class "Default")
      (node (ref "U$2") (pin "2") (pinfunction "2_2") (pintype "bidirectional"))
    )
    (net (code "85") (name "unconnected-(U$2-Pad3)") (class "Default")
      (node (ref "U$2") (pin "3") (pinfunction "3_3") (pintype "bidirectional"))
    )
    (net (code "86") (name "unconnected-(U$2-Pad4)") (class "Default")
      (node (ref "U$2") (pin "4") (pinfunction "4_4") (pintype "bidirectional"))
    )
    (net (code "87") (name "unconnected-(U$2-Pad5)") (class "Default")
      (node (ref "U$2") (pin "5") (pinfunction "5_5") (pintype "bidirectional"))
    )
    (net (code "88") (name "unconnected-(U$2-Pad6)") (class "Default")
      (node (ref "U$2") (pin "6") (pinfunction "6_6") (pintype "bidirectional"))
    )
    (net (code "89") (name "unconnected-(U$2-Pad11)") (class "Default")
      (node (ref "U$2") (pin "11") (pinfunction "11_11") (pintype "bidirectional"))
    )
    (net (code "90") (name "unconnected-(U$2-Pad12)") (class "Default")
      (node (ref "U$2") (pin "12") (pinfunction "12_12") (pintype "bidirectional"))
    )
    (net (code "91") (name "unconnected-(U$2-Pad30)") (class "Default")
      (node (ref "U$2") (pin "30") (pinfunction "30_30") (pintype "bidirectional"))
    )
    (net (code "92") (name "unconnected-(U$2-Pad31)") (class "Default")
      (node (ref "U$2") (pin "31") (pinfunction "31_31") (pintype "bidirectional"))
    )
    (net (code "93") (name "unconnected-(U$2-Pad32)") (class "Default")
      (node (ref "U$2") (pin "32") (pinfunction "32_32") (pintype "bidirectional"))
    )
    (net (code "94") (name "unconnected-(U$2-Pad33)") (class "Default")
      (node (ref "U$2") (pin "33") (pinfunction "33_33") (pintype "bidirectional"))
    )
    (net (code "95") (name "unconnected-(U$2-Pad34)") (class "Default")
      (node (ref "U$2") (pin "34") (pinfunction "34_34") (pintype "bidirectional"))
    )
  )
)
